# 09_Clock.net
KiCad netlist of a schematic drawn in Altium Designer
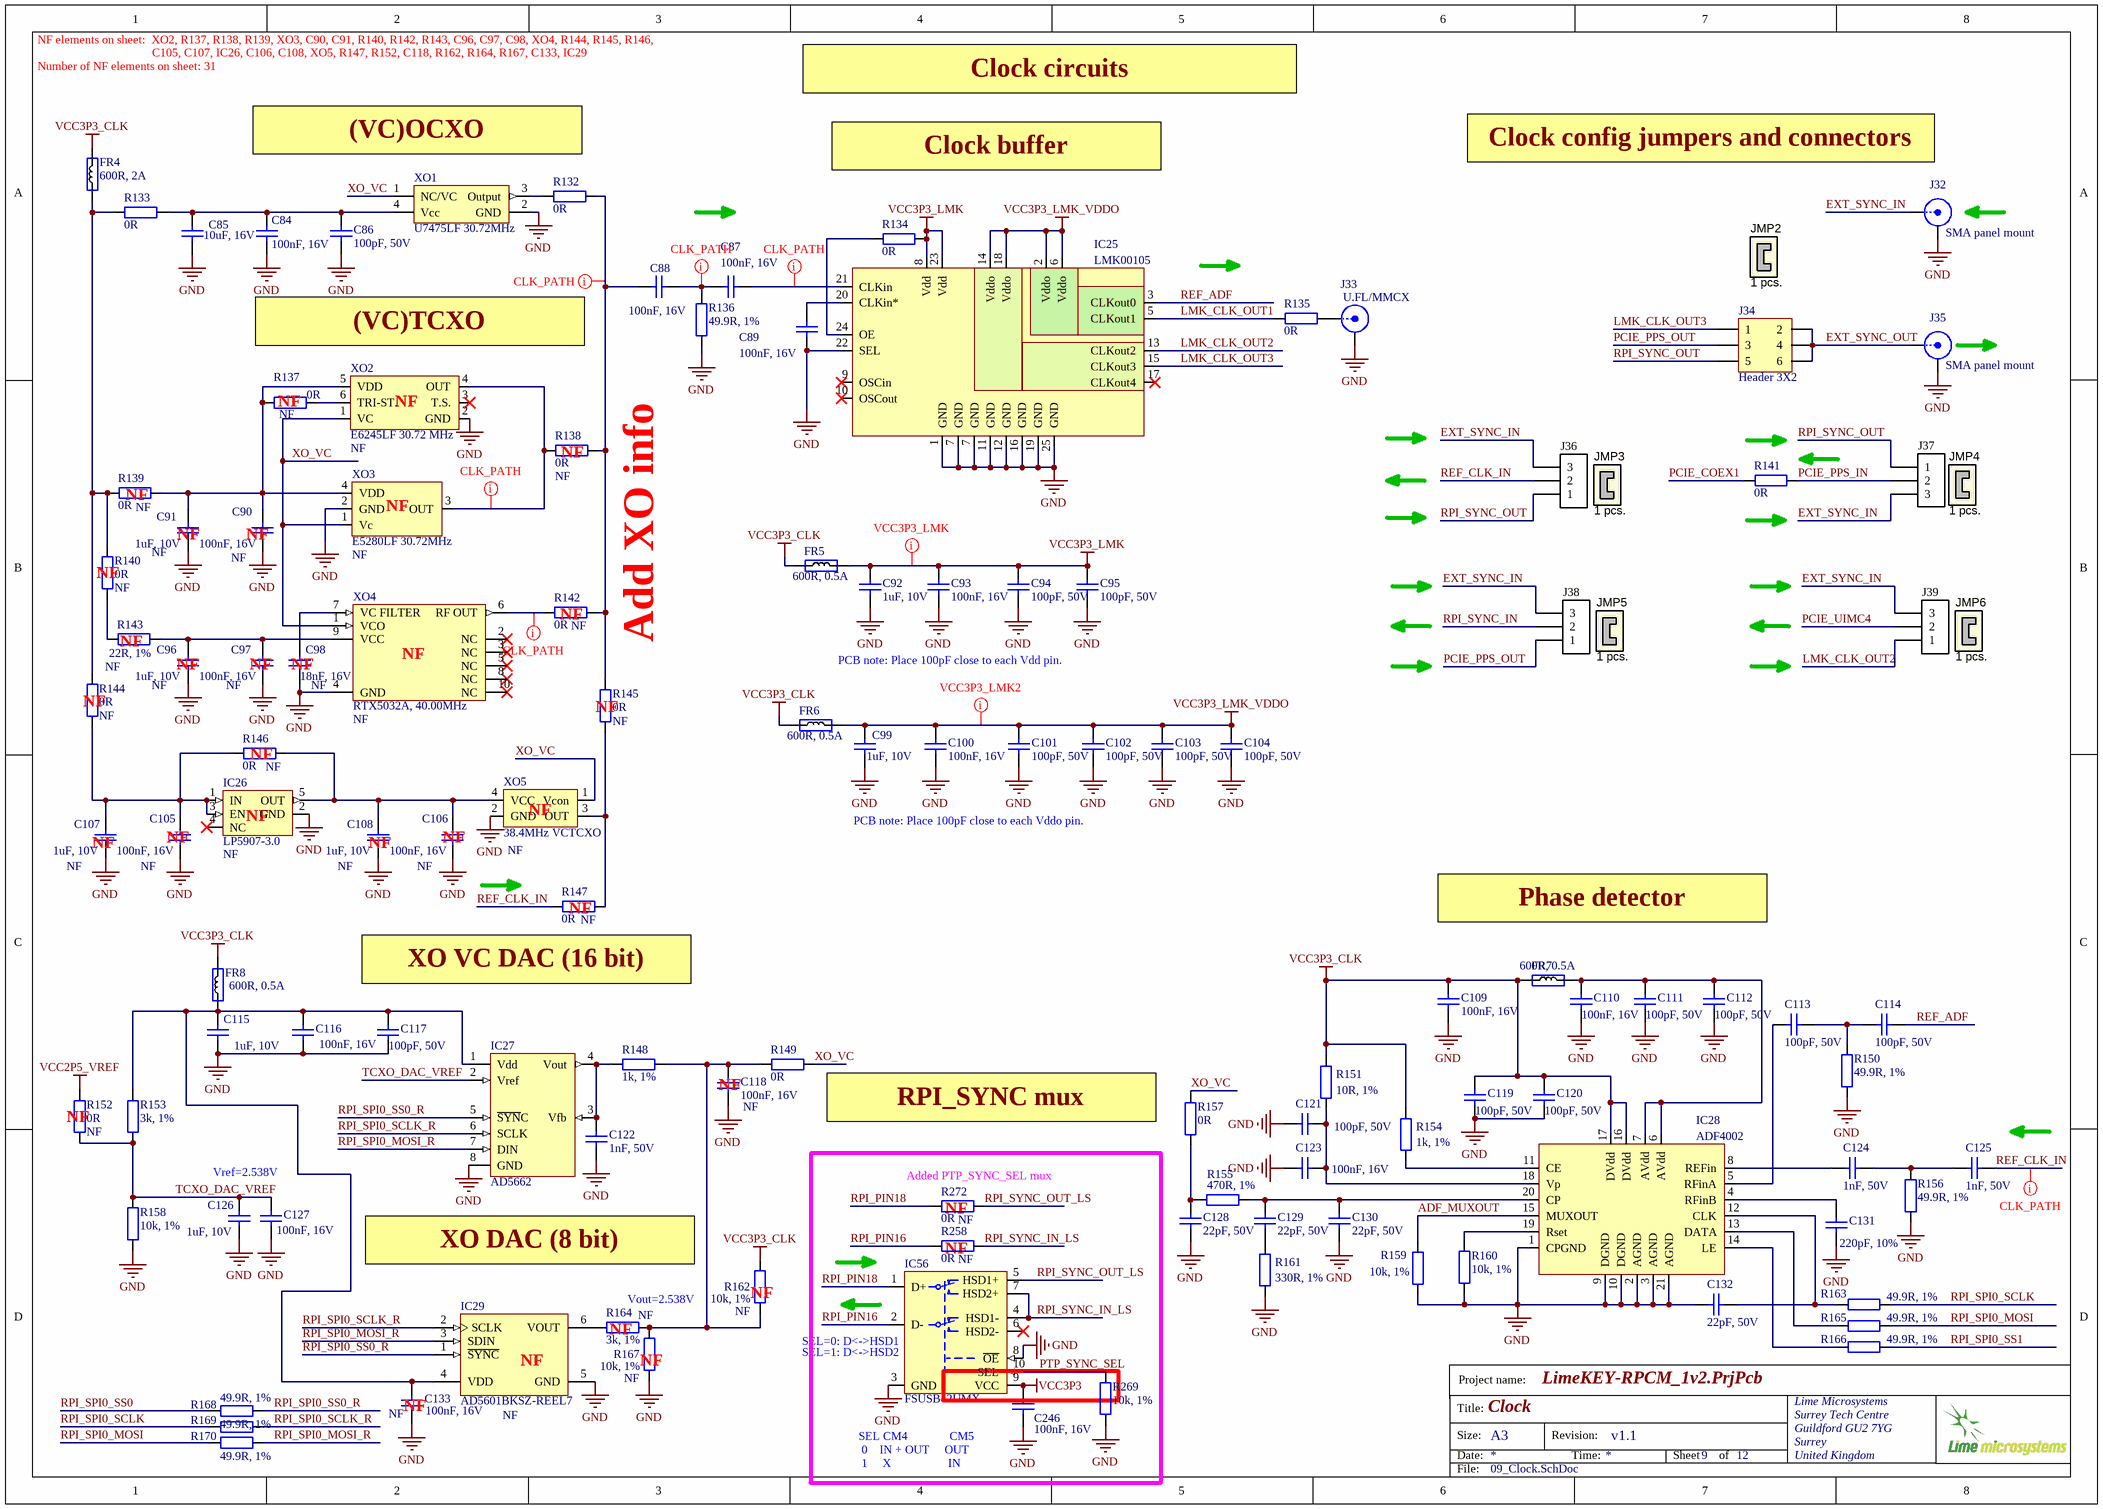
[diagram p0: 09_Clock.SchDoc]

(export (version "E")
  (design (tool "Eeschema 10.0.6"))
  (components
    (comp (ref "C84")
      (value "100nF, 16V")
      (footprint "CAP0402")
      (fields
        (field (name "MANUFACTURER") "Murata Electronics")
        (field (name "TOLERANCE") "10 %")
        (field (name "MANUFACTURER PART NUMBER") "GRM155R71C104KA88D")
      )
      (libsource (lib "LimeMicroAltiumLib_schLib") (part "Cap_0402"))
    )
    (comp (ref "C85")
      (value "10uF, 16V")
      (footprint "CAP0603")
      (fields (field (name "MANUFACTURER") "Yageo") (field (name "TOLERANCE") "±20%"))
      (libsource (lib "LimeMicroAltiumLib_schLib") (part "Cap_0603"))
    )
    (comp (ref "C86")
      (value "100pF, 50V")
      (footprint "CAP0402")
      (fields (field (name "TOLERANCE") "±5%") (field (name "MANUFACTURER") "Yageo"))
      (libsource (lib "LimeMicroAltiumLib_schLib") (part "Cap_0402"))
    )
    (comp (ref "C87")
      (value "100nF, 16V")
      (footprint "CAP0402")
      (fields
        (field (name "MANUFACTURER") "Murata Electronics")
        (field (name "TOLERANCE") "10 %")
        (field (name "MANUFACTURER PART NUMBER") "GRM155R71C104KA88D")
      )
      (libsource (lib "LimeMicroAltiumLib_schLib") (part "Cap_0402"))
    )
    (comp (ref "C88")
      (value "100nF, 16V")
      (footprint "CAP0402")
      (fields
        (field (name "MANUFACTURER") "Murata Electronics")
        (field (name "TOLERANCE") "10 %")
        (field (name "MANUFACTURER PART NUMBER") "GRM155R71C104KA88D")
      )
      (libsource (lib "LimeMicroAltiumLib_schLib") (part "Cap_0402"))
    )
    (comp (ref "C89")
      (value "100nF, 16V")
      (footprint "CAP0402")
      (fields
        (field (name "MANUFACTURER") "Murata Electronics")
        (field (name "TOLERANCE") "10 %")
        (field (name "MANUFACTURER PART NUMBER") "GRM155R71C104KA88D")
      )
      (libsource (lib "LimeMicroAltiumLib_schLib") (part "Cap_0402"))
    )
    (comp (ref "C90")
      (value "100nF, 16V")
      (footprint "CAP0402")
      (fields
        (field (name "ASSEMBLY INFO") "NF")
        (field (name "MANUFACTURER") "Murata Electronics")
        (field (name "TOLERANCE") "10 %")
        (field (name "MANUFACTURER PART NUMBER") "GRM155R71C104KA88D")
      )
      (libsource (lib "LimeMicroAltiumLib_schLib") (part "Cap_0402"))
    )
    (comp (ref "C91")
      (value "1uF, 10V")
      (footprint "CAP0402")
      (description "CAP CER 1UF 10V X5R 0402")
      (fields (field (name "ASSEMBLY INFO") "NF") (field (name "MANUFACTURER") "Yageo"))
      (libsource (lib "LimeMicroAltiumLib_schLib") (part "Cap_0402"))
    )
    (comp (ref "C92")
      (value "1uF, 10V")
      (footprint "CAP0402")
      (description "CAP CER 1UF 10V X5R 0402")
      (fields (field (name "MANUFACTURER") "Yageo") (field (name "TOLERANCE") "±20%"))
      (libsource (lib "LimeMicroAltiumLib_schLib") (part "Cap_0402"))
    )
    (comp (ref "C93")
      (value "100nF, 16V")
      (footprint "CAP0402")
      (fields
        (field (name "MANUFACTURER") "Murata Electronics")
        (field (name "TOLERANCE") "10 %")
        (field (name "MANUFACTURER PART NUMBER") "GRM155R71C104KA88D")
      )
      (libsource (lib "LimeMicroAltiumLib_schLib") (part "Cap_0402"))
    )
    (comp (ref "C94")
      (value "100pF, 50V")
      (footprint "CAP0402")
      (fields (field (name "MANUFACTURER") "Yageo") (field (name "TOLERANCE") "±5%"))
      (libsource (lib "LimeMicroAltiumLib_schLib") (part "Cap_0402"))
    )
    (comp (ref "C95")
      (value "100pF, 50V")
      (footprint "CAP0402")
      (fields (field (name "MANUFACTURER") "Yageo") (field (name "TOLERANCE") "±5%"))
      (libsource (lib "LimeMicroAltiumLib_schLib") (part "Cap_0402"))
    )
    (comp (ref "C96")
      (value "1uF, 10V")
      (footprint "CAP0402")
      (description "CAP CER 1UF 10V X5R 0402")
      (fields (field (name "ASSEMBLY INFO") "NF") (field (name "MANUFACTURER") "Yageo"))
      (libsource (lib "LimeMicroAltiumLib_schLib") (part "Cap_0402"))
    )
    (comp (ref "C97")
      (value "100nF, 16V")
      (footprint "CAP0402")
      (fields
        (field (name "ASSEMBLY INFO") "NF")
        (field (name "MANUFACTURER") "Murata Electronics")
        (field (name "TOLERANCE") "10 %")
        (field (name "MANUFACTURER PART NUMBER") "GRM155R71C104KA88D")
      )
      (libsource (lib "LimeMicroAltiumLib_schLib") (part "Cap_0402"))
    )
    (comp (ref "C98")
      (value "18nF, 16V")
      (footprint "CAP0402")
      (fields
        (field (name "ASSEMBLY INFO") "NF")
        (field (name "MANUFACTURER") "Yageo")
        (field (name "TOLERANCE") "±10%")
      )
      (libsource (lib "LimeMicroAltiumLib_schLib") (part "Cap_0402"))
    )
    (comp (ref "C99")
      (value "1uF, 10V")
      (footprint "CAP0402")
      (description "CAP CER 1UF 10V X5R 0402")
      (fields (field (name "MANUFACTURER") "Yageo") (field (name "TOLERANCE") "±20%"))
      (libsource (lib "LimeMicroAltiumLib_schLib") (part "Cap_0402"))
    )
    (comp (ref "C100")
      (value "100nF, 16V")
      (footprint "CAP0402")
      (fields
        (field (name "MANUFACTURER") "Murata Electronics")
        (field (name "TOLERANCE") "10 %")
        (field (name "MANUFACTURER PART NUMBER") "GRM155R71C104KA88D")
      )
      (libsource (lib "LimeMicroAltiumLib_schLib") (part "Cap_0402"))
    )
    (comp (ref "C101")
      (value "100pF, 50V")
      (footprint "CAP0402")
      (fields (field (name "MANUFACTURER") "Yageo") (field (name "TOLERANCE") "±5%"))
      (libsource (lib "LimeMicroAltiumLib_schLib") (part "Cap_0402"))
    )
    (comp (ref "C102")
      (value "100pF, 50V")
      (footprint "CAP0402")
      (fields (field (name "MANUFACTURER") "Yageo") (field (name "TOLERANCE") "±5%"))
      (libsource (lib "LimeMicroAltiumLib_schLib") (part "Cap_0402"))
    )
    (comp (ref "C103")
      (value "100pF, 50V")
      (footprint "CAP0402")
      (fields (field (name "MANUFACTURER") "Yageo") (field (name "TOLERANCE") "±5%"))
      (libsource (lib "LimeMicroAltiumLib_schLib") (part "Cap_0402"))
    )
    (comp (ref "C104")
      (value "100pF, 50V")
      (footprint "CAP0402")
      (fields (field (name "MANUFACTURER") "Yageo") (field (name "TOLERANCE") "±5%"))
      (libsource (lib "LimeMicroAltiumLib_schLib") (part "Cap_0402"))
    )
    (comp (ref "C105")
      (value "100nF, 16V")
      (footprint "CAP0402")
      (fields
        (field (name "ASSEMBLY INFO") "NF")
        (field (name "MANUFACTURER") "Murata Electronics")
        (field (name "TOLERANCE") "10 %")
        (field (name "MANUFACTURER PART NUMBER") "GRM155R71C104KA88D")
      )
      (libsource (lib "") (part "Cap_0402_1"))
    )
    (comp (ref "C106")
      (value "100nF, 16V")
      (footprint "CAP0402")
      (fields
        (field (name "ASSEMBLY INFO") "NF")
        (field (name "MANUFACTURER") "Murata Electronics")
        (field (name "TOLERANCE") "10 %")
        (field (name "MANUFACTURER PART NUMBER") "GRM155R71C104KA88D")
      )
      (libsource (lib "") (part "Cap_0402_1"))
    )
    (comp (ref "C107")
      (value "1uF, 10V")
      (footprint "CAP0402")
      (fields (field (name "ASSEMBLY INFO") "NF") (field (name "MANUFACTURER") "Yageo"))
      (libsource (lib "") (part "Cap_0402_1"))
    )
    (comp (ref "C108")
      (value "1uF, 10V")
      (footprint "CAP0402")
      (fields (field (name "ASSEMBLY INFO") "NF") (field (name "MANUFACTURER") "Yageo"))
      (libsource (lib "") (part "Cap_0402_1"))
    )
    (comp (ref "C109")
      (value "100nF, 16V")
      (footprint "CAP0402")
      (fields
        (field (name "MANUFACTURER") "Murata Electronics")
        (field (name "TOLERANCE") "10 %")
        (field (name "MANUFACTURER PART NUMBER") "GRM155R71C104KA88D")
      )
      (libsource (lib "LimeMicroAltiumLib_schLib") (part "Cap_0402"))
    )
    (comp (ref "C110")
      (value "100nF, 16V")
      (footprint "CAP0402")
      (fields
        (field (name "MANUFACTURER") "Murata Electronics")
        (field (name "TOLERANCE") "10 %")
        (field (name "MANUFACTURER PART NUMBER") "GRM155R71C104KA88D")
      )
      (libsource (lib "LimeMicroAltiumLib_schLib") (part "Cap_0402"))
    )
    (comp (ref "C111")
      (value "100pF, 50V")
      (footprint "CAP0402")
      (fields (field (name "MANUFACTURER") "Yageo") (field (name "TOLERANCE") "±5%"))
      (libsource (lib "LimeMicroAltiumLib_schLib") (part "Cap_0402"))
    )
    (comp (ref "C112")
      (value "100pF, 50V")
      (footprint "CAP0402")
      (fields (field (name "MANUFACTURER") "Yageo") (field (name "TOLERANCE") "±5%"))
      (libsource (lib "LimeMicroAltiumLib_schLib") (part "Cap_0402"))
    )
    (comp (ref "C113")
      (value "100pF, 50V")
      (footprint "CAP0402")
      (fields (field (name "MANUFACTURER") "Yageo") (field (name "TOLERANCE") "±5%"))
      (libsource (lib "LimeMicroAltiumLib_schLib") (part "Cap_0402"))
    )
    (comp (ref "C114")
      (value "100pF, 50V")
      (footprint "CAP0402")
      (fields (field (name "MANUFACTURER") "Yageo") (field (name "TOLERANCE") "±5%"))
      (libsource (lib "LimeMicroAltiumLib_schLib") (part "Cap_0402"))
    )
    (comp (ref "C115")
      (value "1uF, 10V")
      (footprint "CAP0402")
      (description "CAP CER 1UF 10V X5R 0402")
      (fields (field (name "MANUFACTURER") "Yageo") (field (name "TOLERANCE") "±20%"))
      (libsource (lib "LimeMicroAltiumLib_schLib") (part "Cap_0402"))
    )
    (comp (ref "C116")
      (value "100nF, 16V")
      (footprint "CAP0402")
      (fields
        (field (name "TOLERANCE") "10 %")
        (field (name "MANUFACTURER") "Murata Electronics")
        (field (name "MANUFACTURER PART NUMBER") "GRM155R71C104KA88D")
      )
      (libsource (lib "LimeFPGAboard_schLib") (part "Cap_0603"))
    )
    (comp (ref "C117")
      (value "100pF, 50V")
      (footprint "CAP0402")
      (fields (field (name "MANUFACTURER") "Yageo") (field (name "TOLERANCE") "±5%"))
      (libsource (lib "LimeMicroAltiumLib_schLib") (part "Cap_0402"))
    )
    (comp (ref "C118")
      (value "100nF, 16V")
      (footprint "CAP0402")
      (fields
        (field (name "ASSEMBLY INFO") "NF")
        (field (name "MANUFACTURER") "Murata Electronics")
        (field (name "TOLERANCE") "10 %")
        (field (name "MANUFACTURER PART NUMBER") "GRM155R71C104KA88D")
      )
      (libsource (lib "LimeMicroAltiumLib_schLib") (part "Cap_0402"))
    )
    (comp (ref "C119")
      (value "100pF, 50V")
      (footprint "CAP0402")
      (fields (field (name "MANUFACTURER") "Yageo") (field (name "TOLERANCE") "±5%"))
      (libsource (lib "LimeMicroAltiumLib_schLib") (part "Cap_0402"))
    )
    (comp (ref "C120")
      (value "100pF, 50V")
      (footprint "CAP0402")
      (fields (field (name "MANUFACTURER") "Yageo") (field (name "TOLERANCE") "±5%"))
      (libsource (lib "LimeMicroAltiumLib_schLib") (part "Cap_0402"))
    )
    (comp (ref "C121")
      (value "100pF, 50V")
      (footprint "CAP0402")
      (fields (field (name "MANUFACTURER") "Yageo") (field (name "TOLERANCE") "±5%"))
      (libsource (lib "LimeMicroAltiumLib_schLib") (part "Cap_0402"))
    )
    (comp (ref "C122")
      (value "1nF, 50V")
      (footprint "CAP0402")
      (fields
        (field (name "TOLERANCE") "±10%")
        (field (name "MANUFACTURER") "Murata Electronics North America")
      )
      (libsource (lib "LimeMicroAltiumLib_schLib") (part "Cap_0402"))
    )
    (comp (ref "C123")
      (value "100nF, 16V")
      (footprint "CAP0402")
      (fields
        (field (name "MANUFACTURER") "Murata Electronics")
        (field (name "TOLERANCE") "10 %")
        (field (name "MANUFACTURER PART NUMBER") "GRM155R71C104KA88D")
      )
      (libsource (lib "LimeMicroAltiumLib_schLib") (part "Cap_0402"))
    )
    (comp (ref "C124")
      (value "1nF, 50V")
      (footprint "CAP0402")
      (fields
        (field (name "TOLERANCE") "±10%")
        (field (name "MANUFACTURER") "Murata Electronics North America")
      )
      (libsource (lib "LimeMicroAltiumLib_schLib") (part "Cap_0402"))
    )
    (comp (ref "C125")
      (value "1nF, 50V")
      (footprint "CAP0402")
      (fields
        (field (name "TOLERANCE") "±10%")
        (field (name "MANUFACTURER") "Murata Electronics North America")
      )
      (libsource (lib "LimeMicroAltiumLib_schLib") (part "Cap_0402"))
    )
    (comp (ref "C126")
      (value "1uF, 10V")
      (footprint "CAP0402")
      (description "CAP CER 1UF 10V X5R 0402")
      (fields (field (name "MANUFACTURER") "Yageo") (field (name "TOLERANCE") "±20%"))
      (libsource (lib "LimeMicroAltiumLib_schLib") (part "Cap_0402"))
    )
    (comp (ref "C127")
      (value "100nF, 16V")
      (footprint "CAP0402")
      (fields
        (field (name "TOLERANCE") "10 %")
        (field (name "MANUFACTURER") "Murata Electronics")
        (field (name "MANUFACTURER PART NUMBER") "GRM155R71C104KA88D")
      )
      (libsource (lib "LimeFPGAboard_schLib") (part "Cap_0603"))
    )
    (comp (ref "C128")
      (value "22pF, 50V")
      (footprint "CAP0402")
      (fields (field (name "TOLERANCE") "±5%") (field (name "MANUFACTURER") "Yageo"))
      (libsource (lib "LimeMicroAltiumLib_schLib") (part "Cap_0402"))
    )
    (comp (ref "C129")
      (value "22pF, 50V")
      (footprint "CAP0402")
      (fields (field (name "TOLERANCE") "±5%") (field (name "MANUFACTURER") "Yageo"))
      (libsource (lib "LimeMicroAltiumLib_schLib") (part "Cap_0402"))
    )
    (comp (ref "C130")
      (value "22pF, 50V")
      (footprint "CAP0402")
      (fields (field (name "TOLERANCE") "±5%") (field (name "MANUFACTURER") "Yageo"))
      (libsource (lib "LimeMicroAltiumLib_schLib") (part "Cap_0402"))
    )
    (comp (ref "C131")
      (value "220pF, 10%")
      (footprint "CAP0402")
      (fields (field (name "MANUFACTURER") "Yageo") (field (name "TOLERANCE") "±10%"))
      (libsource (lib "LimeMicroAltiumLib_schLib") (part "Cap_0402"))
    )
    (comp (ref "C132")
      (value "22pF, 50V")
      (footprint "CAP0402")
      (fields (field (name "TOLERANCE") "±5%") (field (name "MANUFACTURER") "Yageo"))
      (libsource (lib "LimeMicroAltiumLib_schLib") (part "Cap_0402"))
    )
    (comp (ref "C133")
      (value "100nF, 16V")
      (footprint "CAP0402")
      (fields
        (field (name "TOLERANCE") "10 %")
        (field (name "MANUFACTURER") "Murata Electronics")
        (field (name "MANUFACTURER PART NUMBER") "GRM155R71C104KA88D")
        (field (name "ASSEMBLY INFO") "NF")
      )
      (libsource (lib "LimeFPGAboard_schLib") (part "Cap_0603"))
    )
    (comp (ref "C246")
      (value "100nF, 16V")
      (footprint "CAP0402")
      (fields
        (field (name "MANUFACTURER") "Murata Electronics")
        (field (name "TOLERANCE") "10 %")
        (field (name "MANUFACTURER PART NUMBER") "GRM155R71C104KA88D")
      )
      (libsource (lib "LimeMicroAltiumLib_schLib") (part "Cap_0402"))
    )
    (comp (ref "FR4")
      (value "600R, 2A")
      (footprint "RES0805")
      (fields (field (name "MANUFACTURER") "TDK Corporation"))
      (libsource (lib "LimeFPGAboard_schLib") (part "Ferrite"))
    )
    (comp (ref "FR5")
      (value "600R, 0.5A")
      (footprint "RES0402")
      (fields (field (name "MANUFACTURER") "Murata") (field (name "TOLERANCE") "25%"))
      (libsource (lib "LimeMicroAltiumLib_schLib") (part "Ferrite"))
    )
    (comp (ref "FR6")
      (value "600R, 0.5A")
      (footprint "RES0402")
      (fields (field (name "MANUFACTURER") "Murata") (field (name "TOLERANCE") "25%"))
      (libsource (lib "LimeMicroAltiumLib_schLib") (part "Ferrite"))
    )
    (comp (ref "FR7")
      (value "600R, 0.5A")
      (footprint "RES0402")
      (fields (field (name "MANUFACTURER") "Murata") (field (name "TOLERANCE") "25%"))
      (libsource (lib "LimeMicroAltiumLib_schLib") (part "Ferrite"))
    )
    (comp (ref "FR8")
      (value "600R, 0.5A")
      (footprint "RES0402")
      (fields (field (name "MANUFACTURER") "Murata") (field (name "TOLERANCE") "25%"))
      (libsource (lib "LimeMicroAltiumLib_schLib") (part "Ferrite"))
    )
    (comp (ref "IC25")
      (value "LMK00105")
      (footprint "LMK00105SQ")
      (fields (field (name "MANUFACTURER") "Texas Instruments"))
      (libsource (lib "LimeMicroAltiumLib_schLib") (part "LMK00105"))
    )
    (comp (ref "IC26")
      (value "LP5907-3.0")
      (footprint "SOT23-5")
      (fields (field (name "MANUFACTURER") "Texas Instruments") (field (name "ASSEMBLY INFO") "NF"))
      (libsource (lib "LimeMicroAltiumLib_schLib_r01") (part "LP5907"))
    )
    (comp (ref "IC27")
      (value "AD5662")
      (footprint "AD5662_SOT23-8")
      (fields (field (name "MANUFACTURER") "Analog Devices Inc."))
      (libsource (lib "LimeMicroAltiumLib_schLib") (part "AD5662"))
    )
    (comp (ref "IC28")
      (value "ADF4002")
      (footprint "ADF4002")
      (fields (field (name "MANUFACTURER") "Analog Devices Inc"))
      (libsource (lib "LimeMicroAltiumLib_schLib") (part "ADF4002"))
    )
    (comp (ref "IC29")
      (value "AD5601BKSZ-REEL7")
      (footprint "AD5601_SOT23-6")
      (fields
        (field (name "GENERIC PART NUMBER") "AD5601")
        (field (name "MANUFACTURER") "Analog Devices")
        (field (name "ASSEMBLY INFO") "NF")
      )
      (libsource (lib "LimeMicroAltiumLib_schLib") (part "AD5601BKSZ-REEL7"))
    )
    (comp (ref "IC56")
      (value "FSUSB42UMX")
      (footprint "FSUSB42UMX")
      (fields (field (name "MANUFACTURER") "ON Semiconductor") (field (name "BASE PART NUMBER") "FSUSB42"))
      (libsource (lib "LimeMicroAltiumLib_schLib_r01") (part "FSUSB42UMX"))
    )
    (comp (ref "J32")
      (value "SMA panel mount")
      (footprint "SMA_connector_side")
      (description "CONN SMA JACK STR 50OHM EDGE MNT")
      (fields (field (name "MANUFACTURER") "Linx"))
      (libsource (lib "LimeMicroAltiumLib_schLib") (part "RF_IF_connector"))
    )
    (comp (ref "J33")
      (value "U.FL/MMCX")
      (footprint "MMCX_UFL_conn_u")
      (description "CONN UMC RCPT STR 50 OHM SMD")
      (fields (field (name "MANUFACTURER") "Molex, LLC"))
      (libsource (lib "") (part "RF_IF_connector_1"))
    )
    (comp (ref "J34")
      (value "Header 3X2")
      (footprint "Header3x2")
      (description "Header, 2-Pin, Dual row")
      (fields
        (field (name "MANUFACTURER PART NUMBER") "PH2-06-UA")
        (field (name "MANUFACTURER") "Adam Equipment")
      )
      (libsource (lib "LimeMicroAltiumLib_schLib_r01") (part "Header 3X2"))
    )
    (comp (ref "J35")
      (value "SMA panel mount")
      (footprint "SMA_connector_side")
      (description "CONN SMA JACK STR 50OHM EDGE MNT")
      (fields (field (name "MANUFACTURER") "Linx"))
      (libsource (lib "LimeMicroAltiumLib_schLib") (part "RF_IF_connector"))
    )
    (comp (ref "J36")
      (value "Header 3x1 pin")
      (footprint "HDR_1x3")
      (description "Header, 3-pin")
      (fields
        (field (name "MANUFACTURER PART NUMBER") "61300311121")
        (field (name "MANUFACTURER") "Wurth Electronics")
      )
      (libsource (lib "") (part "Header3P_1"))
    )
    (comp (ref "J37")
      (value "Header 3x1 pin")
      (footprint "HDR_1x3")
      (description "Header, 3-pin")
      (fields
        (field (name "MANUFACTURER PART NUMBER") "61300311121")
        (field (name "MANUFACTURER") "Wurth Electronics")
      )
      (libsource (lib "LimeMicroAltiumLib_schLib_r04") (part "Header3P"))
    )
    (comp (ref "J38")
      (value "Header 3x1 pin")
      (footprint "HDR_1x3")
      (description "Header, 3-pin")
      (fields
        (field (name "MANUFACTURER PART NUMBER") "61300311121")
        (field (name "MANUFACTURER") "Wurth Electronics")
      )
      (libsource (lib "") (part "Header3P_1"))
    )
    (comp (ref "J39")
      (value "Header 3x1 pin")
      (footprint "HDR_1x3")
      (description "Header, 3-pin")
      (fields
        (field (name "MANUFACTURER PART NUMBER") "61300311121")
        (field (name "MANUFACTURER") "Wurth Electronics")
      )
      (libsource (lib "") (part "Header3P_1"))
    )
    (comp (ref "JMP2")
      (value "1 pcs.")
      (description "Shorting Jumper, 2-position, 1.27mm pitch")
      (fields (field (name "MANUFACTURER") "Sullins"))
      (libsource (lib "LimeMicroAltiumLib_schLib") (part "JUMP_2P_CONN_HEADER"))
    )
    (comp (ref "JMP3")
      (value "1 pcs.")
      (description "Shorting Jumper, 2-position, 1.27mm pitch")
      (fields (field (name "MANUFACTURER") "Sullins"))
      (libsource (lib "LimeMicroAltiumLib_schLib") (part "JUMP_2P_CONN_HEADER"))
    )
    (comp (ref "JMP4")
      (value "1 pcs.")
      (description "Shorting Jumper, 2-position, 1.27mm pitch")
      (fields (field (name "MANUFACTURER") "Sullins"))
      (libsource (lib "LimeMicroAltiumLib_schLib") (part "JUMP_2P_CONN_HEADER"))
    )
    (comp (ref "JMP5")
      (value "1 pcs.")
      (description "Shorting Jumper, 2-position, 1.27mm pitch")
      (fields (field (name "MANUFACTURER") "Sullins"))
      (libsource (lib "LimeMicroAltiumLib_schLib") (part "JUMP_2P_CONN_HEADER"))
    )
    (comp (ref "JMP6")
      (value "1 pcs.")
      (description "Shorting Jumper, 2-position, 1.27mm pitch")
      (fields (field (name "MANUFACTURER") "Sullins"))
      (libsource (lib "LimeMicroAltiumLib_schLib") (part "JUMP_2P_CONN_HEADER"))
    )
    (comp (ref "R132")
      (value "0R")
      (footprint "RES0402_v2")
      (fields (field (name "MANUFACTURER") "Yageo") (field (name "TOLERANCE") "Jumper"))
      (libsource (lib "LimeMicroAltiumLib_schLib") (part "Res_0402"))
    )
    (comp (ref "R133")
      (value "0R")
      (footprint "RES0402")
      (fields (field (name "MANUFACTURER") "Yageo") (field (name "TOLERANCE") "Jumper"))
      (libsource (lib "LimeMicroAltiumLib_schLib") (part "Res_0402"))
    )
    (comp (ref "R134")
      (value "0R")
      (footprint "RES0402")
      (fields (field (name "MANUFACTURER") "Yageo") (field (name "TOLERANCE") "Jumper"))
      (libsource (lib "LimeMicroAltiumLib_schLib") (part "Res_0402"))
    )
    (comp (ref "R135")
      (value "0R")
      (footprint "RES0402")
      (fields (field (name "MANUFACTURER") "Yageo") (field (name "TOLERANCE") "Jumper"))
      (libsource (lib "") (part "Res_0402_1"))
    )
    (comp (ref "R136")
      (value "49.9R, 1%")
      (footprint "RES0402")
      (fields
        (field (name "TOLERANCE") "±1%")
        (field (name "MANUFACTURER") "Samsung Electro-Mechanics America, Inc.")
      )
      (libsource (lib "LimeMicroAltiumLib_schLib") (part "Res_0402"))
    )
    (comp (ref "R137")
      (value "0R")
      (footprint "RES0402")
      (fields
        (field (name "ASSEMBLY INFO") "NF")
        (field (name "MANUFACTURER") "Yageo")
        (field (name "TOLERANCE") "Jumper")
      )
      (libsource (lib "LimeMicroAltiumLib_schLib") (part "Res_0402"))
    )
    (comp (ref "R138")
      (value "0R")
      (footprint "RES0402_v2")
      (fields
        (field (name "ASSEMBLY INFO") "NF")
        (field (name "MANUFACTURER") "Yageo")
        (field (name "TOLERANCE") "Jumper")
      )
      (libsource (lib "LimeMicroAltiumLib_schLib") (part "Res_0402"))
    )
    (comp (ref "R139")
      (value "0R")
      (footprint "RES0402")
      (fields
        (field (name "MANUFACTURER") "Yageo")
        (field (name "TOLERANCE") "Jumper")
        (field (name "ASSEMBLY INFO") "NF")
      )
      (libsource (lib "LimeMicroAltiumLib_schLib") (part "Res_0402"))
    )
    (comp (ref "R140")
      (value "0R")
      (footprint "RES0402")
      (fields
        (field (name "ASSEMBLY INFO") "NF")
        (field (name "MANUFACTURER") "Yageo")
        (field (name "TOLERANCE") "Jumper")
      )
      (libsource (lib "LimeMicroAltiumLib_schLib") (part "Res_0402"))
    )
    (comp (ref "R141")
      (value "0R")
      (footprint "RES0402")
      (fields (field (name "MANUFACTURER") "Yageo") (field (name "TOLERANCE") "Jumper"))
      (libsource (lib "") (part "Res_0402_1"))
    )
    (comp (ref "R142")
      (value "0R")
      (footprint "RES0402_v2")
      (fields
        (field (name "ASSEMBLY INFO") "NF")
        (field (name "MANUFACTURER") "Yageo")
        (field (name "TOLERANCE") "Jumper")
      )
      (libsource (lib "LimeMicroAltiumLib_schLib") (part "Res_0402"))
    )
    (comp (ref "R143")
      (value "22R, 1%")
      (footprint "RES0402")
      (fields
        (field (name "TOLERANCE") "±1%")
        (field (name "MANUFACTURER") "Yageo")
        (field (name "ASSEMBLY INFO") "NF")
      )
      (libsource (lib "LimeFPGAboard_schLib") (part "Res_0402"))
    )
    (comp (ref "R144")
      (value "0R")
      (footprint "RES0402")
      (fields
        (field (name "MANUFACTURER") "Yageo")
        (field (name "TOLERANCE") "Jumper")
        (field (name "ASSEMBLY INFO") "NF")
      )
      (libsource (lib "") (part "Res_0402_1"))
    )
    (comp (ref "R145")
      (value "0R")
      (footprint "RES0402_v2")
      (fields
        (field (name "ASSEMBLY INFO") "NF")
        (field (name "MANUFACTURER") "Yageo")
        (field (name "TOLERANCE") "Jumper")
      )
      (libsource (lib "") (part "Res_0402_1"))
    )
    (comp (ref "R146")
      (value "0R")
      (footprint "RES0402")
      (fields
        (field (name "MANUFACTURER") "Yageo")
        (field (name "TOLERANCE") "Jumper")
        (field (name "ASSEMBLY INFO") "NF")
      )
      (libsource (lib "") (part "Res_0402_1"))
    )
    (comp (ref "R147")
      (value "0R")
      (footprint "RES0402_v2")
      (fields
        (field (name "ASSEMBLY INFO") "NF")
        (field (name "MANUFACTURER") "Yageo")
        (field (name "TOLERANCE") "Jumper")
      )
      (libsource (lib "LimeMicroAltiumLib_schLib") (part "Res_0402"))
    )
    (comp (ref "R148")
      (value "1k, 1%")
      (footprint "RES0402")
      (fields (field (name "MANUFACTURER") "Stackpole Electronics Inc") (field (name "TOLERANCE") "±1%"))
      (libsource (lib "LimeMicroAltiumLib_schLib") (part "Res_0402"))
    )
    (comp (ref "R149")
      (value "0R")
      (footprint "RES0402")
      (fields (field (name "MANUFACTURER") "Yageo") (field (name "TOLERANCE") "Jumper"))
      (libsource (lib "LimeMicroAltiumLib_schLib") (part "Res_0402"))
    )
    (comp (ref "R150")
      (value "49.9R, 1%")
      (footprint "RES0402")
      (fields
        (field (name "TOLERANCE") "±1%")
        (field (name "MANUFACTURER") "Samsung Electro-Mechanics America, Inc.")
      )
      (libsource (lib "LimeMicroAltiumLib_schLib") (part "Res_0402"))
    )
    (comp (ref "R151")
      (value "10R, 1%")
      (footprint "RES0402")
      (fields (field (name "MANUFACTURER") "Stackpole Electronics") (field (name "TOLERANCE") "1%"))
      (libsource (lib "LimeMicroAltiumLib_schLib") (part "Res_0402"))
    )
    (comp (ref "R152")
      (value "0R")
      (footprint "RES0402_v2")
      (fields
        (field (name "ASSEMBLY INFO") "NF")
        (field (name "MANUFACTURER") "Yageo")
        (field (name "TOLERANCE") "Jumper")
      )
      (libsource (lib "LimeMicroAltiumLib_schLib") (part "Res_0402"))
    )
    (comp (ref "R153")
      (value "3k, 1%")
      (footprint "RES0402")
      (fields (field (name "TOLERANCE") "±1%") (field (name "MANUFACTURER") "Vishay Dale"))
      (libsource (lib "LimeMicroAltiumLib_schLib") (part "Res_0402"))
    )
    (comp (ref "R154")
      (value "1k, 1%")
      (footprint "RES0402")
      (fields (field (name "MANUFACTURER") "Stackpole Electronics Inc") (field (name "TOLERANCE") "±1%"))
      (libsource (lib "LimeMicroAltiumLib_schLib") (part "Res_0402"))
    )
    (comp (ref "R155")
      (value "470R, 1%")
      (footprint "RES0402")
      (fields (field (name "TOLERANCE") "1%") (field (name "MANUFACTURER") "Yageo"))
      (libsource (lib "") (part "Res_0402_1"))
    )
    (comp (ref "R156")
      (value "49.9R, 1%")
      (footprint "RES0402")
      (fields
        (field (name "TOLERANCE") "±1%")
        (field (name "MANUFACTURER") "Samsung Electro-Mechanics America, Inc.")
      )
      (libsource (lib "LimeMicroAltiumLib_schLib") (part "Res_0402"))
    )
    (comp (ref "R157")
      (value "0R")
      (footprint "RES0402")
      (fields (field (name "MANUFACTURER") "Yageo") (field (name "TOLERANCE") "Jumper"))
      (libsource (lib "LimeMicroAltiumLib_schLib") (part "Res_0402"))
    )
    (comp (ref "R158")
      (value "10k, 1%")
      (footprint "RES0402")
      (fields (field (name "MANUFACTURER") "Yageo") (field (name "TOLERANCE") "±1%"))
      (libsource (lib "LimeMicroAltiumLib_schLib") (part "Res_0402"))
    )
    (comp (ref "R159")
      (value "10k, 1%")
      (footprint "RES0402")
      (fields (field (name "MANUFACTURER") "Yageo") (field (name "TOLERANCE") "±1%"))
      (libsource (lib "LimeMicroAltiumLib_schLib") (part "Res_0402"))
    )
    (comp (ref "R160")
      (value "10k, 1%")
      (footprint "RES0402")
      (fields (field (name "MANUFACTURER") "Yageo") (field (name "TOLERANCE") "±1%"))
      (libsource (lib "LimeMicroAltiumLib_schLib") (part "Res_0402"))
    )
    (comp (ref "R161")
      (value "330R, 1%")
      (footprint "RES0402")
      (fields (field (name "MANUFACTURER") "Yageo") (field (name "TOLERANCE") "1%"))
      (libsource (lib "LimeMicroAltiumLib_schLib") (part "Res_0402"))
    )
    (comp (ref "R162")
      (value "10k, 1%")
      (footprint "RES0402")
      (fields
        (field (name "ASSEMBLY INFO") "NF")
        (field (name "MANUFACTURER") "Yageo")
        (field (name "TOLERANCE") "±1%")
      )
      (libsource (lib "LimeMicroAltiumLib_schLib") (part "Res_0402"))
    )
    (comp (ref "R163")
      (value "49.9R, 1%")
      (footprint "RES0402")
      (fields
        (field (name "TOLERANCE") "±1%")
        (field (name "MANUFACTURER") "Samsung Electro-Mechanics America, Inc.")
      )
      (libsource (lib "LimeMicroAltiumLib_schLib") (part "Res_0402"))
    )
    (comp (ref "R164")
      (value "3k, 1%")
      (footprint "RES0402")
      (fields
        (field (name "ASSEMBLY INFO") "NF")
        (field (name "TOLERANCE") "±1%")
        (field (name "MANUFACTURER") "Vishay Dale")
      )
      (libsource (lib "LimeMicroAltiumLib_schLib") (part "Res_0402"))
    )
    (comp (ref "R165")
      (value "49.9R, 1%")
      (footprint "RES0402")
      (fields
        (field (name "TOLERANCE") "±1%")
        (field (name "MANUFACTURER") "Samsung Electro-Mechanics America, Inc.")
      )
      (libsource (lib "LimeMicroAltiumLib_schLib") (part "Res_0402"))
    )
    (comp (ref "R166")
      (value "49.9R, 1%")
      (footprint "RES0402")
      (fields
        (field (name "TOLERANCE") "±1%")
        (field (name "MANUFACTURER") "Samsung Electro-Mechanics America, Inc.")
      )
      (libsource (lib "LimeMicroAltiumLib_schLib") (part "Res_0402"))
    )
    (comp (ref "R167")
      (value "10k, 1%")
      (footprint "RES0402")
      (fields
        (field (name "ASSEMBLY INFO") "NF")
        (field (name "MANUFACTURER") "Yageo")
        (field (name "TOLERANCE") "±1%")
      )
      (libsource (lib "LimeMicroAltiumLib_schLib") (part "Res_0402"))
    )
    (comp (ref "R168")
      (value "49.9R, 1%")
      (footprint "RES0402")
      (fields
        (field (name "TOLERANCE") "±1%")
        (field (name "MANUFACTURER") "Samsung Electro-Mechanics America, Inc.")
      )
      (libsource (lib "LimeMicroAltiumLib_schLib") (part "Res_0402"))
    )
    (comp (ref "R169")
      (value "49.9R, 1%")
      (footprint "RES0402")
      (fields
        (field (name "TOLERANCE") "±1%")
        (field (name "MANUFACTURER") "Samsung Electro-Mechanics America, Inc.")
      )
      (libsource (lib "LimeMicroAltiumLib_schLib") (part "Res_0402"))
    )
    (comp (ref "R170")
      (value "49.9R, 1%")
      (footprint "RES0402")
      (fields
        (field (name "TOLERANCE") "±1%")
        (field (name "MANUFACTURER") "Samsung Electro-Mechanics America, Inc.")
      )
      (libsource (lib "LimeMicroAltiumLib_schLib") (part "Res_0402"))
    )
    (comp (ref "R258")
      (value "0R")
      (footprint "RES0402")
      (fields
        (field (name "ASSEMBLY INFO") "NF")
        (field (name "MANUFACTURER") "Yageo")
        (field (name "TOLERANCE") "Jumper")
      )
      (libsource (lib "") (part "Res_0402_1"))
    )
    (comp (ref "R269")
      (value "10k, 1%")
      (footprint "RES0402")
      (fields (field (name "MANUFACTURER") "Yageo") (field (name "TOLERANCE") "±1%"))
      (libsource (lib "LimeMicroAltiumLib_schLib") (part "Res_0402"))
    )
    (comp (ref "R272")
      (value "0R")
      (footprint "RES0402")
      (fields
        (field (name "ASSEMBLY INFO") "NF")
        (field (name "MANUFACTURER") "Yageo")
        (field (name "TOLERANCE") "Jumper")
      )
      (libsource (lib "") (part "Res_0402_1"))
    )
    (comp (ref "XO1")
      (value "U7475LF 30.72MHz")
      (footprint "AOCJYR-10.000MHz")
      (fields (field (name "MANUFACTURER") "Rakon"))
      (libsource (lib "LimeMicroAltiumLib_schLib") (part "AOCJYR-10.000MHz"))
    )
    (comp (ref "XO2")
      (value "E6245LF 30.72 MHz")
      (footprint "RAKON_RPT7050A")
      (fields (field (name "ASSEMBLY INFO") "NF") (field (name "MANUFACTURER") "Rakon"))
      (libsource (lib "LimeMicroAltiumLib_schLib") (part "RPT7050A"))
    )
    (comp (ref "XO3")
      (value "E5280LF 30.72MHz")
      (footprint "RAKON_TXCO")
      (fields (field (name "ASSEMBLY INFO") "NF") (field (name "MANUFACTURER") "Rakon"))
      (libsource (lib "LimeMicroAltiumLib_schLib") (part "TXCO"))
    )
    (comp (ref "XO4")
      (value "RTX5032A, 40.00MHz")
      (footprint "RAKON_RTX5032A")
      (fields (field (name "ASSEMBLY INFO") "NF") (field (name "MANUFACTURER") "Rakon"))
      (libsource (lib "LimeMicroAltiumLib_schLib") (part "Rakon_RTX5032A"))
    )
    (comp (ref "XO5")
      (value "38.4MHz VCTCXO")
      (footprint "CRYSTAL_4-LCC_2P5x2P0")
      (description "Oscillator Crystal")
      (fields (field (name "MANUFACTURER") "Abracon") (field (name "ASSEMBLY INFO") "NF"))
      (libsource (lib "LimeMicroAltiumLib_schLib_r01") (part "ASVTX-12-A-38.400MHZ-H10-T_CRYSTAL"))
    )
  )
  (nets
    (net (code "1") (name "/ADF_MUXOUT") (class "Default")
      (node (ref "IC28") (pin "15") (pinfunction "MUXOUT_15") (pintype "passive"))
      (node (ref "R159") (pin "1") (pinfunction "1_1") (pintype "passive"))
    )
    (net (code "2") (name "/EXT_SYNC_IN") (class "Default")
      (node (ref "J32") (pin "1") (pinfunction "X_1") (pintype "passive"))
      (node (ref "J36") (pin "3") (pinfunction "3_3") (pintype "passive"))
      (node (ref "J37") (pin "3") (pinfunction "3_3") (pintype "passive"))
      (node (ref "J38") (pin "3") (pinfunction "3_3") (pintype "passive"))
      (node (ref "J39") (pin "3") (pinfunction "3_3") (pintype "passive"))
    )
    (net (code "3") (name "/EXT_SYNC_OUT") (class "Default")
      (node (ref "J34") (pin "2") (pinfunction "2_2") (pintype "passive"))
      (node (ref "J34") (pin "4") (pinfunction "4_4") (pintype "passive"))
      (node (ref "J34") (pin "6") (pinfunction "6_6") (pintype "passive"))
      (node (ref "J35") (pin "1") (pinfunction "X_1") (pintype "passive"))
    )
    (net (code "4") (name "/LMK_CLK_OUT1") (class "Default")
      (node (ref "IC25") (pin "5") (pinfunction "CLKout1_5") (pintype "passive"))
      (node (ref "R135") (pin "2") (pinfunction "2_2") (pintype "passive"))
    )
    (net (code "5") (name "/LMK_CLK_OUT2") (class "Default")
      (node (ref "IC25") (pin "13") (pinfunction "CLKout2_13") (pintype "passive"))
      (node (ref "J39") (pin "1") (pinfunction "1_1") (pintype "passive"))
    )
    (net (code "6") (name "/LMK_CLK_OUT3") (class "Default")
      (node (ref "IC25") (pin "15") (pinfunction "CLKout3_15") (pintype "passive"))
      (node (ref "J34") (pin "1") (pinfunction "1_1") (pintype "passive"))
    )
    (net (code "7") (name "/PCIE_COEX1") (class "Default")
      (node (ref "R141") (pin "2") (pinfunction "2_2") (pintype "passive"))
    )
    (net (code "9") (name "/PCIE_PPS_OUT") (class "Default")
      (node (ref "J34") (pin "3") (pinfunction "3_3") (pintype "passive"))
      (node (ref "J38") (pin "1") (pinfunction "1_1") (pintype "passive"))
    )
    (net (code "10") (name "/PCIE_UIMC4") (class "Default")
      (node (ref "J39") (pin "2") (pinfunction "2_2") (pintype "passive"))
    )
    (net (code "11") (name "/PTP_SYNC_SEL") (class "Default")
      (node (ref "IC56") (pin "10") (pinfunction "SEL_10") (pintype "input"))
      (node (ref "R269") (pin "1") (pinfunction "1_1") (pintype "passive"))
    )
    (net (code "12") (name "/REF_ADF") (class "Default")
      (node (ref "C114") (pin "2") (pinfunction "2_2") (pintype "passive"))
      (node (ref "IC25") (pin "3") (pinfunction "CLKout0_3") (pintype "passive"))
    )
    (net (code "13") (name "/REF_CLK_IN") (class "Default")
      (node (ref "C125") (pin "2") (pinfunction "2_2") (pintype "passive"))
      (node (ref "J36") (pin "2") (pinfunction "2_2") (pintype "passive"))
      (node (ref "R147") (pin "2") (pinfunction "2_2") (pintype "passive"))
    )
    (net (code "14") (name "/RPI_PIN16") (class "Default")
      (node (ref "IC56") (pin "2") (pinfunction "D-_2") (pintype "passive"))
      (node (ref "R258") (pin "2") (pinfunction "2_2") (pintype "passive"))
    )
    (net (code "15") (name "/RPI_PIN18") (class "Default")
      (node (ref "IC56") (pin "1") (pinfunction "D+_1") (pintype "passive"))
      (node (ref "R272") (pin "2") (pinfunction "2_2") (pintype "passive"))
    )
    (net (code "16") (name "/RPI_SPI0_MOSI") (class "Default")
      (node (ref "R165") (pin "1") (pinfunction "1_1") (pintype "passive"))
      (node (ref "R170") (pin "2") (pinfunction "2_2") (pintype "passive"))
    )
    (net (code "17") (name "/RPI_SPI0_MOSI_R") (class "Default")
      (node (ref "IC27") (pin "7") (pinfunction "DIN_7") (pintype "input"))
      (node (ref "IC29") (pin "3") (pinfunction "SDIN_3") (pintype "input"))
      (node (ref "R170") (pin "1") (pinfunction "1_1") (pintype "passive"))
    )
    (net (code "18") (name "/RPI_SPI0_SCLK") (class "Default")
      (node (ref "R163") (pin "1") (pinfunction "1_1") (pintype "passive"))
      (node (ref "R169") (pin "2") (pinfunction "2_2") (pintype "passive"))
    )
    (net (code "19") (name "/RPI_SPI0_SCLK_R") (class "Default")
      (node (ref "IC27") (pin "6") (pinfunction "SCLK_6") (pintype "input"))
      (node (ref "IC29") (pin "2") (pinfunction "SCLK_2") (pintype "input"))
      (node (ref "R169") (pin "1") (pinfunction "1_1") (pintype "passive"))
    )
    (net (code "20") (name "/RPI_SPI0_SS0") (class "Default")
      (node (ref "R168") (pin "2") (pinfunction "2_2") (pintype "passive"))
    )
    (net (code "21") (name "/RPI_SPI0_SS0_R") (class "Default")
      (node (ref "IC27") (pin "5") (pinfunction "~{SYN}C_5") (pintype "input"))
      (node (ref "IC29") (pin "1") (pinfunction "~{SYNC}_1") (pintype "input"))
      (node (ref "R168") (pin "1") (pinfunction "1_1") (pintype "passive"))
    )
    (net (code "22") (name "/RPI_SPI0_SS1") (class "Default")
      (node (ref "R166") (pin "1") (pinfunction "1_1") (pintype "passive"))
    )
    (net (code "23") (name "/RPI_SYNC_IN") (class "Default")
      (node (ref "J38") (pin "2") (pinfunction "2_2") (pintype "passive"))
    )
    (net (code "24") (name "/RPI_SYNC_IN_LS") (class "Default")
      (node (ref "IC56") (pin "4") (pinfunction "HSD1-_4") (pintype "passive"))
      (node (ref "IC56") (pin "7") (pinfunction "HSD2+_7") (pintype "passive"))
      (node (ref "R258") (pin "1") (pinfunction "1_1") (pintype "passive"))
    )
    (net (code "25") (name "/RPI_SYNC_OUT") (class "Default")
      (node (ref "J34") (pin "5") (pinfunction "5_5") (pintype "passive"))
      (node (ref "J36") (pin "1") (pinfunction "1_1") (pintype "passive"))
      (node (ref "J37") (pin "1") (pinfunction "1_1") (pintype "passive"))
    )
    (net (code "26") (name "/RPI_SYNC_OUT_LS") (class "Default")
      (node (ref "IC56") (pin "5") (pinfunction "HSD1+_5") (pintype "passive"))
      (node (ref "R272") (pin "1") (pinfunction "1_1") (pintype "passive"))
    )
    (net (code "27") (name "/TCXO_DAC_VREF") (class "Default")
      (node (ref "C126") (pin "2") (pinfunction "2_2") (pintype "passive"))
      (node (ref "C127") (pin "1") (pinfunction "1_1") (pintype "passive"))
      (node (ref "IC27") (pin "2") (pinfunction "Vref_2") (pintype "input"))
      (node (ref "R152") (pin "1") (pinfunction "1_1") (pintype "passive"))
      (node (ref "R153") (pin "1") (pinfunction "1_1") (pintype "passive"))
      (node (ref "R158") (pin "1") (pinfunction "1_1") (pintype "passive"))
    )
    (net (code "28") (name "/XO_VC") (class "Default")
      (node (ref "R149") (pin "1") (pinfunction "1_1") (pintype "passive"))
      (node (ref "R157") (pin "2") (pinfunction "2_2") (pintype "passive"))
      (node (ref "XO1") (pin "1") (pinfunction "NC/VC_1") (pintype "passive"))
      (node (ref "XO2") (pin "1") (pinfunction "VC_1") (pintype "passive"))
      (node (ref "XO3") (pin "1") (pinfunction "Vc_1") (pintype "passive"))
      (node (ref "XO4") (pin "1") (pinfunction "VCO_1") (pintype "input"))
      (node (ref "XO5") (pin "1") (pinfunction "Vcon_1") (pintype "passive"))
    )
    (net (code "29") (name "GND") (class "Default")
      (node (ref "C100") (pin "1") (pinfunction "1_1") (pintype "passive"))
      (node (ref "C101") (pin "1") (pinfunction "1_1") (pintype "passive"))
      (node (ref "C102") (pin "1") (pinfunction "1_1") (pintype "passive"))
      (node (ref "C103") (pin "1") (pinfunction "1_1") (pintype "passive"))
      (node (ref "C104") (pin "1") (pinfunction "1_1") (pintype "passive"))
      (node (ref "C105") (pin "1") (pinfunction "1_1") (pintype "passive"))
      (node (ref "C106") (pin "1") (pinfunction "1_1") (pintype "passive"))
      (node (ref "C107") (pin "1") (pinfunction "1_1") (pintype "passive"))
      (node (ref "C108") (pin "1") (pinfunction "1_1") (pintype "passive"))
      (node (ref "C109") (pin "1") (pinfunction "1_1") (pintype "passive"))
      (node (ref "C110") (pin "1") (pinfunction "1_1") (pintype "passive"))
      (node (ref "C111") (pin "2") (pinfunction "2_2") (pintype "passive"))
      (node (ref "C112") (pin "2") (pinfunction "2_2") (pintype "passive"))
      (node (ref "C115") (pin "1") (pinfunction "1_1") (pintype "passive"))
      (node (ref "C116") (pin "2") (pinfunction "2_2") (pintype "passive"))
      (node (ref "C117") (pin "2") (pinfunction "2_2") (pintype "passive"))
      (node (ref "C118") (pin "1") (pinfunction "1_1") (pintype "passive"))
      (node (ref "C119") (pin "2") (pinfunction "2_2") (pintype "passive"))
      (node (ref "C120") (pin "2") (pinfunction "2_2") (pintype "passive"))
      (node (ref "C121") (pin "1") (pinfunction "1_1") (pintype "passive"))
      (node (ref "C122") (pin "2") (pinfunction "2_2") (pintype "passive"))
      (node (ref "C123") (pin "2") (pinfunction "2_2") (pintype "passive"))
      (node (ref "C126") (pin "1") (pinfunction "1_1") (pintype "passive"))
      (node (ref "C127") (pin "2") (pinfunction "2_2") (pintype "passive"))
      (node (ref "C128") (pin "1") (pinfunction "1_1") (pintype "passive"))
      (node (ref "C130") (pin "1") (pinfunction "1_1") (pintype "passive"))
      (node (ref "C131") (pin "2") (pinfunction "2_2") (pintype "passive"))
      (node (ref "C132") (pin "2") (pinfunction "2_2") (pintype "passive"))
      (node (ref "C133") (pin "2") (pinfunction "2_2") (pintype "passive"))
      (node (ref "C246") (pin "2") (pinfunction "2_2") (pintype "passive"))
      (node (ref "C84") (pin "1") (pinfunction "1_1") (pintype "passive"))
      (node (ref "C85") (pin "1") (pinfunction "1_1") (pintype "passive"))
      (node (ref "C86") (pin "2") (pinfunction "2_2") (pintype "passive"))
      (node (ref "C89") (pin "1") (pinfunction "1_1") (pintype "passive"))
      (node (ref "C90") (pin "1") (pinfunction "1_1") (pintype "passive"))
      (node (ref "C91") (pin "1") (pinfunction "1_1") (pintype "passive"))
      (node (ref "C92") (pin "1") (pinfunction "1_1") (pintype "passive"))
      (node (ref "C93") (pin "1") (pinfunction "1_1") (pintype "passive"))
      (node (ref "C94") (pin "1") (pinfunction "1_1") (pintype "passive"))
      (node (ref "C95") (pin "1") (pinfunction "1_1") (pintype "passive"))
      (node (ref "C96") (pin "1") (pinfunction "1_1") (pintype "passive"))
      (node (ref "C97") (pin "1") (pinfunction "1_1") (pintype "passive"))
      (node (ref "C98") (pin "1") (pinfunction "1_1") (pintype "passive"))
      (node (ref "C99") (pin "1") (pinfunction "1_1") (pintype "passive"))
      (node (ref "IC25") (pin "1") (pinfunction "GND_1") (pintype "passive"))
      (node (ref "IC25") (pin "11") (pinfunction "GND_11") (pintype "passive"))
      (node (ref "IC25") (pin "12") (pinfunction "GND_12") (pintype "passive"))
      (node (ref "IC25") (pin "16") (pinfunction "GND_16") (pintype "passive"))
      (node (ref "IC25") (pin "19") (pinfunction "GND_19") (pintype "passive"))
      (node (ref "IC25") (pin "22") (pinfunction "SEL_22") (pintype "passive"))
      (node (ref "IC25") (pin "25") (pinfunction "GND_25") (pintype "passive"))
      (node (ref "IC25") (pin "7") (pinfunction "GND_7") (pintype "passive"))
      (node (ref "IC26") (pin "2") (pinfunction "GND_2") (pintype "passive"))
      (node (ref "IC27") (pin "8") (pinfunction "GND_8") (pintype "passive"))
      (node (ref "IC28") (pin "1") (pinfunction "CPGND_1") (pintype "passive"))
      (node (ref "IC28") (pin "10") (pinfunction "DGND_10") (pintype "passive"))
      (node (ref "IC28") (pin "2") (pinfunction "AGND_2") (pintype "passive"))
      (node (ref "IC28") (pin "21") (pinfunction "AGND_21") (pintype "passive"))
      (node (ref "IC28") (pin "3") (pinfunction "AGND_3") (pintype "passive"))
      (node (ref "IC28") (pin "9") (pinfunction "DGND_9") (pintype "passive"))
      (node (ref "IC29") (pin "5") (pinfunction "GND_5") (pintype "power_in"))
      (node (ref "IC56") (pin "3") (pinfunction "GND_3") (pintype "passive"))
      (node (ref "IC56") (pin "8") (pinfunction "~{OE}_8") (pintype "input"))
      (node (ref "J32") (pin "2") (pinfunction "Y_2") (pintype "passive"))
      (node (ref "J33") (pin "2") (pinfunction "Y_2") (pintype "passive"))
      (node (ref "J35") (pin "2") (pinfunction "Y_2") (pintype "passive"))
      (node (ref "R136") (pin "1") (pinfunction "1_1") (pintype "passive"))
      (node (ref "R150") (pin "1") (pinfunction "1_1") (pintype "passive"))
      (node (ref "R156") (pin "1") (pinfunction "1_1") (pintype "passive"))
      (node (ref "R158") (pin "2") (pinfunction "2_2") (pintype "passive"))
      (node (ref "R159") (pin "2") (pinfunction "2_2") (pintype "passive"))
      (node (ref "R160") (pin "2") (pinfunction "2_2") (pintype "passive"))
      (node (ref "R161") (pin "1") (pinfunction "1_1") (pintype "passive"))
      (node (ref "R167") (pin "2") (pinfunction "2_2") (pintype "passive"))
      (node (ref "R269") (pin "2") (pinfunction "2_2") (pintype "passive"))
      (node (ref "XO1") (pin "2") (pinfunction "GND_2") (pintype "passive"))
      (node (ref "XO2") (pin "2") (pinfunction "GND_2") (pintype "passive"))
      (node (ref "XO3") (pin "2") (pinfunction "GND_2") (pintype "passive"))
      (node (ref "XO4") (pin "4") (pinfunction "GND_4") (pintype "passive"))
      (node (ref "XO5") (pin "2") (pinfunction "GND_2") (pintype "passive"))
    )
    (net (code "30") (name "Net-(C87-Pad2)") (class "Default")
      (node (ref "C87") (pin "2") (pinfunction "2_2") (pintype "passive"))
      (node (ref "C88") (pin "1") (pinfunction "1_1") (pintype "passive"))
      (node (ref "R136") (pin "2") (pinfunction "2_2") (pintype "passive"))
    )
    (net (code "31") (name "Net-(C88-Pad2)") (class "Default")
      (node (ref "C88") (pin "2") (pinfunction "2_2") (pintype "passive"))
      (node (ref "R132") (pin "1") (pinfunction "1_1") (pintype "passive"))
      (node (ref "R138") (pin "1") (pinfunction "1_1") (pintype "passive"))
      (node (ref "R142") (pin "2") (pinfunction "2_2") (pintype "passive"))
      (node (ref "R145") (pin "1") (pinfunction "1_1") (pintype "passive"))
    )
    (net (code "32") (name "Net-(C110-Pad2)") (class "Default")
      (node (ref "C110") (pin "2") (pinfunction "2_2") (pintype "passive"))
      (node (ref "C111") (pin "1") (pinfunction "1_1") (pintype "passive"))
      (node (ref "C112") (pin "1") (pinfunction "1_1") (pintype "passive"))
      (node (ref "FR7") (pin "2") (pinfunction "2_2") (pintype "passive"))
      (node (ref "IC28") (pin "6") (pinfunction "AVdd_6") (pintype "passive"))
      (node (ref "IC28") (pin "7") (pinfunction "AVdd_7") (pintype "passive"))
    )
    (net (code "33") (name "Net-(C113-Pad2)") (class "Default")
      (node (ref "C113") (pin "2") (pinfunction "2_2") (pintype "passive"))
      (node (ref "C114") (pin "1") (pinfunction "1_1") (pintype "passive"))
      (node (ref "R150") (pin "2") (pinfunction "2_2") (pintype "passive"))
    )
    (net (code "34") (name "Net-(C118-Pad2)") (class "Default")
      (node (ref "C118") (pin "2") (pinfunction "2_2") (pintype "passive"))
      (node (ref "R148") (pin "1") (pinfunction "1_1") (pintype "passive"))
      (node (ref "R149") (pin "2") (pinfunction "2_2") (pintype "passive"))
      (node (ref "R162") (pin "2") (pinfunction "2_2") (pintype "passive"))
      (node (ref "R164") (pin "1") (pinfunction "1_1") (pintype "passive"))
      (node (ref "R167") (pin "1") (pinfunction "1_1") (pintype "passive"))
    )
    (net (code "35") (name "Net-(C124-Pad2)") (class "Default")
      (node (ref "C124") (pin "2") (pinfunction "2_2") (pintype "passive"))
      (node (ref "C125") (pin "1") (pinfunction "1_1") (pintype "passive"))
      (node (ref "R156") (pin "2") (pinfunction "2_2") (pintype "passive"))
    )
    (net (code "36") (name "Net-(C128-Pad2)") (class "Default")
      (node (ref "C128") (pin "2") (pinfunction "2_2") (pintype "passive"))
      (node (ref "R155") (pin "2") (pinfunction "2_2") (pintype "passive"))
      (node (ref "R157") (pin "1") (pinfunction "1_1") (pintype "passive"))
    )
    (net (code "37") (name "Net-(C129-Pad1)") (class "Default")
      (node (ref "C129") (pin "1") (pinfunction "1_1") (pintype "passive"))
      (node (ref "R161") (pin "2") (pinfunction "2_2") (pintype "passive"))
    )
    (net (code "38") (name "Net-(FR4-Pad2)") (class "Default")
      (node (ref "FR4") (pin "2") (pinfunction "2_2") (pintype "passive"))
      (node (ref "R133") (pin "1") (pinfunction "1_1") (pintype "passive"))
      (node (ref "R139") (pin "2") (pinfunction "2_2") (pintype "passive"))
      (node (ref "R140") (pin "1") (pinfunction "1_1") (pintype "passive"))
      (node (ref "R144") (pin "1") (pinfunction "1_1") (pintype "passive"))
    )
    (net (code "39") (name "Net-(IC25-CLKin)") (class "Default")
      (node (ref "C87") (pin "1") (pinfunction "1_1") (pintype "passive"))
      (node (ref "IC25") (pin "21") (pinfunction "CLKin_21") (pintype "passive"))
    )
    (net (code "40") (name "Net-(IC25-CLKin*)") (class "Default")
      (node (ref "C89") (pin "2") (pinfunction "2_2") (pintype "passive"))
      (node (ref "IC25") (pin "20") (pinfunction "CLKin*_20") (pintype "passive"))
    )
    (net (code "41") (name "Net-(IC25-OE)") (class "Default")
      (node (ref "IC25") (pin "24") (pinfunction "OE_24") (pintype "passive"))
      (node (ref "R134") (pin "1") (pinfunction "1_1") (pintype "passive"))
    )
    (net (code "42") (name "Net-(IC26-EN)") (class "Default")
      (node (ref "C105") (pin "2") (pinfunction "2_2") (pintype "passive"))
      (node (ref "C107") (pin "2") (pinfunction "2_2") (pintype "passive"))
      (node (ref "IC26") (pin "1") (pinfunction "IN_1") (pintype "input"))
      (node (ref "IC26") (pin "3") (pinfunction "EN_3") (pintype "input"))
      (node (ref "R144") (pin "2") (pinfunction "2_2") (pintype "passive"))
      (node (ref "R146") (pin "2") (pinfunction "2_2") (pintype "passive"))
    )
    (net (code "43") (name "Net-(IC26-OUT)") (class "Default")
      (node (ref "C106") (pin "2") (pinfunction "2_2") (pintype "passive"))
      (node (ref "C108") (pin "2") (pinfunction "2_2") (pintype "passive"))
      (node (ref "IC26") (pin "5") (pinfunction "OUT_5") (pintype "output"))
      (node (ref "R146") (pin "1") (pinfunction "1_1") (pintype "passive"))
      (node (ref "XO5") (pin "4") (pinfunction "VCC_4") (pintype "passive"))
    )
    (net (code "44") (name "Net-(IC27-Vdd)") (class "Default")
      (node (ref "C115") (pin "2") (pinfunction "2_2") (pintype "passive"))
      (node (ref "C116") (pin "1") (pinfunction "1_1") (pintype "passive"))
      (node (ref "C117") (pin "1") (pinfunction "1_1") (pintype "passive"))
      (node (ref "C133") (pin "1") (pinfunction "1_1") (pintype "passive"))
      (node (ref "FR8") (pin "1") (pinfunction "1_1") (pintype "passive"))
      (node (ref "IC27") (pin "1") (pinfunction "Vdd_1") (pintype "power_in"))
      (node (ref "IC29") (pin "4") (pinfunction "VDD_4") (pintype "power_in"))
      (node (ref "R153") (pin "2") (pinfunction "2_2") (pintype "passive"))
    )
    (net (code "45") (name "Net-(IC27-Vfb)") (class "Default")
      (node (ref "C122") (pin "1") (pinfunction "1_1") (pintype "passive"))
      (node (ref "IC27") (pin "3") (pinfunction "Vfb_3") (pintype "input"))
      (node (ref "IC27") (pin "4") (pinfunction "Vout_4") (pintype "output"))
      (node (ref "R148") (pin "2") (pinfunction "2_2") (pintype "passive"))
    )
    (net (code "46") (name "Net-(IC28-CE)") (class "Default")
      (node (ref "IC28") (pin "11") (pinfunction "CE_11") (pintype "passive"))
      (node (ref "R154") (pin "1") (pinfunction "1_1") (pintype "passive"))
    )
    (net (code "47") (name "Net-(IC28-CLK)") (class "Default")
      (node (ref "C132") (pin "1") (pinfunction "1_1") (pintype "passive"))
      (node (ref "IC28") (pin "12") (pinfunction "CLK_12") (pintype "passive"))
      (node (ref "R163") (pin "2") (pinfunction "2_2") (pintype "passive"))
    )
    (net (code "48") (name "Net-(IC28-CP)") (class "Default")
      (node (ref "C129") (pin "2") (pinfunction "2_2") (pintype "passive"))
      (node (ref "C130") (pin "2") (pinfunction "2_2") (pintype "passive"))
      (node (ref "IC28") (pin "20") (pinfunction "CP_20") (pintype "passive"))
      (node (ref "R155") (pin "1") (pinfunction "1_1") (pintype "passive"))
    )
    (net (code "49") (name "Net-(IC28-DATA)") (class "Default")
      (node (ref "IC28") (pin "13") (pinfunction "DATA_13") (pintype "passive"))
      (node (ref "R165") (pin "2") (pinfunction "2_2") (pintype "passive"))
    )
    (net (code "50") (name "Net-(IC28-LE)") (class "Default")
      (node (ref "IC28") (pin "14") (pinfunction "LE_14") (pintype "passive"))
      (node (ref "R166") (pin "2") (pinfunction "2_2") (pintype "passive"))
    )
    (net (code "51") (name "Net-(IC28-REFin)") (class "Default")
      (node (ref "C124") (pin "1") (pinfunction "1_1") (pintype "passive"))
      (node (ref "IC28") (pin "8") (pinfunction "REFin_8") (pintype "passive"))
    )
    (net (code "52") (name "Net-(IC28-RFinA)") (class "Default")
      (node (ref "C113") (pin "1") (pinfunction "1_1") (pintype "passive"))
      (node (ref "IC28") (pin "5") (pinfunction "RFinA_5") (pintype "passive"))
    )
    (net (code "53") (name "Net-(IC28-RFinB)") (class "Default")
      (node (ref "C131") (pin "1") (pinfunction "1_1") (pintype "passive"))
      (node (ref "IC28") (pin "4") (pinfunction "RFinB_4") (pintype "passive"))
    )
    (net (code "54") (name "Net-(IC28-Rset)") (class "Default")
      (node (ref "IC28") (pin "19") (pinfunction "Rset_19") (pintype "passive"))
      (node (ref "R160") (pin "1") (pinfunction "1_1") (pintype "passive"))
    )
    (net (code "55") (name "Net-(IC28-Vp)") (class "Default")
      (node (ref "C121") (pin "2") (pinfunction "2_2") (pintype "passive"))
      (node (ref "C123") (pin "1") (pinfunction "1_1") (pintype "passive"))
      (node (ref "IC28") (pin "18") (pinfunction "Vp_18") (pintype "passive"))
      (node (ref "R151") (pin "1") (pinfunction "1_1") (pintype "passive"))
    )
    (net (code "56") (name "Net-(IC29-VOUT)") (class "Default")
      (node (ref "IC29") (pin "6") (pinfunction "VOUT_6") (pintype "tri_state"))
      (node (ref "R164") (pin "2") (pinfunction "2_2") (pintype "passive"))
    )
    (net (code "57") (name "Net-(J33-X)") (class "Default")
      (node (ref "J33") (pin "1") (pinfunction "X_1") (pintype "passive"))
      (node (ref "R135") (pin "1") (pinfunction "1_1") (pintype "passive"))
    )
    (net (code "58") (name "Net-(J37-Pad2)") (class "Default")
      (node (ref "J37") (pin "2") (pinfunction "2_2") (pintype "passive"))
      (node (ref "R141") (pin "1") (pinfunction "1_1") (pintype "passive"))
    )
    (net (code "59") (name "Net-(R140-Pad2)") (class "Default")
      (node (ref "R140") (pin "2") (pinfunction "2_2") (pintype "passive"))
      (node (ref "R143") (pin "1") (pinfunction "1_1") (pintype "passive"))
    )
    (net (code "60") (name "Net-(XO1-Output)") (class "Default")
      (node (ref "R132") (pin "2") (pinfunction "2_2") (pintype "passive"))
      (node (ref "XO1") (pin "3") (pinfunction "Output_3") (pintype "output"))
    )
    (net (code "61") (name "Net-(XO1-Vcc)") (class "Default")
      (node (ref "C84") (pin "2") (pinfunction "2_2") (pintype "passive"))
      (node (ref "C85") (pin "2") (pinfunction "2_2") (pintype "passive"))
      (node (ref "C86") (pin "1") (pinfunction "1_1") (pintype "passive"))
      (node (ref "R133") (pin "2") (pinfunction "2_2") (pintype "passive"))
      (node (ref "XO1") (pin "4") (pinfunction "Vcc_4") (pintype "power_in"))
    )
    (net (code "62") (name "Net-(XO2-OUT)") (class "Default")
      (node (ref "R138") (pin "2") (pinfunction "2_2") (pintype "passive"))
      (node (ref "XO2") (pin "4") (pinfunction "OUT_4") (pintype "passive"))
      (node (ref "XO3") (pin "3") (pinfunction "OUT_3") (pintype "passive"))
    )
    (net (code "63") (name "Net-(XO2-TRI-ST.)") (class "Default")
      (node (ref "R137") (pin "1") (pinfunction "1_1") (pintype "passive"))
      (node (ref "XO2") (pin "6") (pinfunction "TRI-ST._6") (pintype "passive"))
    )
    (net (code "64") (name "Net-(XO2-VDD)") (class "Default")
      (node (ref "C90") (pin "2") (pinfunction "2_2") (pintype "passive"))
      (node (ref "C91") (pin "2") (pinfunction "2_2") (pintype "passive"))
      (node (ref "R137") (pin "2") (pinfunction "2_2") (pintype "passive"))
      (node (ref "R139") (pin "1") (pinfunction "1_1") (pintype "passive"))
      (node (ref "XO2") (pin "5") (pinfunction "VDD_5") (pintype "passive"))
      (node (ref "XO3") (pin "4") (pinfunction "VDD_4") (pintype "passive"))
    )
    (net (code "65") (name "Net-(XO4-RF_OUT)") (class "Default")
      (node (ref "R142") (pin "1") (pinfunction "1_1") (pintype "passive"))
      (node (ref "XO4") (pin "6") (pinfunction "RF_OUT_6") (pintype "output"))
    )
    (net (code "66") (name "Net-(XO4-VCC)") (class "Default")
      (node (ref "C96") (pin "2") (pinfunction "2_2") (pintype "passive"))
      (node (ref "C97") (pin "2") (pinfunction "2_2") (pintype "passive"))
      (node (ref "R143") (pin "2") (pinfunction "2_2") (pintype "passive"))
      (node (ref "XO4") (pin "9") (pinfunction "VCC_9") (pintype "power_in"))
    )
    (net (code "67") (name "Net-(XO4-VC_FILTER)") (class "Default")
      (node (ref "C98") (pin "2") (pinfunction "2_2") (pintype "passive"))
      (node (ref "XO4") (pin "7") (pinfunction "VC_FILTER_7") (pintype "input"))
    )
    (net (code "68") (name "Net-(XO5-OUT)") (class "Default")
      (node (ref "R145") (pin "2") (pinfunction "2_2") (pintype "passive"))
      (node (ref "R147") (pin "1") (pinfunction "1_1") (pintype "passive"))
      (node (ref "XO5") (pin "3") (pinfunction "OUT_3") (pintype "passive"))
    )
    (net (code "69") (name "VCC2P5_VREF") (class "Default")
      (node (ref "R152") (pin "2") (pinfunction "2_2") (pintype "passive"))
    )
    (net (code "70") (name "VCC3P3") (class "Default")
      (node (ref "C246") (pin "1") (pinfunction "1_1") (pintype "passive"))
      (node (ref "IC56") (pin "9") (pinfunction "VCC_9") (pintype "power_in"))
    )
    (net (code "71") (name "VCC3P3_CLK") (class "Default")
      (node (ref "C109") (pin "2") (pinfunction "2_2") (pintype "passive"))
      (node (ref "C119") (pin "1") (pinfunction "1_1") (pintype "passive"))
      (node (ref "C120") (pin "1") (pinfunction "1_1") (pintype "passive"))
      (node (ref "FR4") (pin "1") (pinfunction "1_1") (pintype "passive"))
      (node (ref "FR5") (pin "1") (pinfunction "1_1") (pintype "passive"))
      (node (ref "FR6") (pin "1") (pinfunction "1_1") (pintype "passive"))
      (node (ref "FR7") (pin "1") (pinfunction "1_1") (pintype "passive"))
      (node (ref "FR8") (pin "2") (pinfunction "2_2") (pintype "passive"))
      (node (ref "IC28") (pin "16") (pinfunction "DVdd_16") (pintype "passive"))
      (node (ref "IC28") (pin "17") (pinfunction "DVdd_17") (pintype "passive"))
      (node (ref "R151") (pin "2") (pinfunction "2_2") (pintype "passive"))
      (node (ref "R154") (pin "2") (pinfunction "2_2") (pintype "passive"))
      (node (ref "R162") (pin "1") (pinfunction "1_1") (pintype "passive"))
    )
    (net (code "72") (name "VCC3P3_LMK") (class "Default")
      (node (ref "C92") (pin "2") (pinfunction "2_2") (pintype "passive"))
      (node (ref "C93") (pin "2") (pinfunction "2_2") (pintype "passive"))
      (node (ref "C94") (pin "2") (pinfunction "2_2") (pintype "passive"))
      (node (ref "C95") (pin "2") (pinfunction "2_2") (pintype "passive"))
      (node (ref "FR5") (pin "2") (pinfunction "2_2") (pintype "passive"))
      (node (ref "IC25") (pin "23") (pinfunction "Vdd_23") (pintype "passive"))
      (node (ref "IC25") (pin "8") (pinfunction "Vdd_8") (pintype "passive"))
      (node (ref "R134") (pin "2") (pinfunction "2_2") (pintype "passive"))
    )
    (net (code "73") (name "VCC3P3_LMK_VDDO") (class "Default")
      (node (ref "C100") (pin "2") (pinfunction "2_2") (pintype "passive"))
      (node (ref "C101") (pin "2") (pinfunction "2_2") (pintype "passive"))
      (node (ref "C102") (pin "2") (pinfunction "2_2") (pintype "passive"))
      (node (ref "C103") (pin "2") (pinfunction "2_2") (pintype "passive"))
      (node (ref "C104") (pin "2") (pinfunction "2_2") (pintype "passive"))
      (node (ref "C99") (pin "2") (pinfunction "2_2") (pintype "passive"))
      (node (ref "FR6") (pin "2") (pinfunction "2_2") (pintype "passive"))
      (node (ref "IC25") (pin "14") (pinfunction "Vddo_14") (pintype "passive"))
      (node (ref "IC25") (pin "18") (pinfunction "Vddo_18") (pintype "passive"))
      (node (ref "IC25") (pin "2") (pinfunction "Vddo_2") (pintype "passive"))
      (node (ref "IC25") (pin "6") (pinfunction "Vddo_6") (pintype "passive"))
    )
    (net (code "74") (name "unconnected-(IC25-CLKout4-Pad17)") (class "Default")
      (node (ref "IC25") (pin "17") (pinfunction "CLKout4_17") (pintype "passive+no_connect"))
    )
    (net (code "75") (name "unconnected-(IC25-OSCin-Pad9)") (class "Default")
      (node (ref "IC25") (pin "9") (pinfunction "OSCin_9") (pintype "passive+no_connect"))
    )
    (net (code "76") (name "unconnected-(IC25-OSCout-Pad10)") (class "Default")
      (node (ref "IC25") (pin "10") (pinfunction "OSCout_10") (pintype "passive+no_connect"))
    )
    (net (code "77") (name "unconnected-(IC26-NC-Pad4)") (class "Default")
      (node (ref "IC26") (pin "4") (pinfunction "NC_4") (pintype "passive+no_connect"))
    )
    (net (code "78") (name "unconnected-(IC56-HSD2--Pad6)") (class "Default")
      (node (ref "IC56") (pin "6") (pinfunction "HSD2-_6") (pintype "passive+no_connect"))
    )
    (net (code "79") (name "unconnected-(JMP2-Pad1)") (class "Default")
      (node (ref "JMP2") (pin "1") (pinfunction "1_1") (pintype "passive"))
    )
    (net (code "80") (name "unconnected-(JMP2-Pad2)") (class "Default")
      (node (ref "JMP2") (pin "2") (pinfunction "2_2") (pintype "passive"))
    )
    (net (code "81") (name "unconnected-(JMP3-Pad1)") (class "Default")
      (node (ref "JMP3") (pin "1") (pinfunction "1_1") (pintype "passive"))
    )
    (net (code "82") (name "unconnected-(JMP3-Pad2)") (class "Default")
      (node (ref "JMP3") (pin "2") (pinfunction "2_2") (pintype "passive"))
    )
    (net (code "83") (name "unconnected-(JMP4-Pad1)") (class "Default")
      (node (ref "JMP4") (pin "1") (pinfunction "1_1") (pintype "passive"))
    )
    (net (code "84") (name "unconnected-(JMP4-Pad2)") (class "Default")
      (node (ref "JMP4") (pin "2") (pinfunction "2_2") (pintype "passive"))
    )
    (net (code "85") (name "unconnected-(JMP5-Pad1)") (class "Default")
      (node (ref "JMP5") (pin "1") (pinfunction "1_1") (pintype "passive"))
    )
    (net (code "86") (name "unconnected-(JMP5-Pad2)") (class "Default")
      (node (ref "JMP5") (pin "2") (pinfunction "2_2") (pintype "passive"))
    )
    (net (code "87") (name "unconnected-(JMP6-Pad1)") (class "Default")
      (node (ref "JMP6") (pin "1") (pinfunction "1_1") (pintype "passive"))
    )
    (net (code "88") (name "unconnected-(JMP6-Pad2)") (class "Default")
      (node (ref "JMP6") (pin "2") (pinfunction "2_2") (pintype "passive"))
    )
    (net (code "89") (name "unconnected-(XO2-T.S.-Pad3)") (class "Default")
      (node (ref "XO2") (pin "3") (pinfunction "T.S._3") (pintype "passive+no_connect"))
    )
    (net (code "90") (name "unconnected-(XO4-NC-Pad2)") (class "Default")
      (node (ref "XO4") (pin "2") (pinfunction "NC_2") (pintype "passive+no_connect"))
    )
    (net (code "91") (name "unconnected-(XO4-NC-Pad3)") (class "Default")
      (node (ref "XO4") (pin "3") (pinfunction "NC_3") (pintype "passive+no_connect"))
    )
    (net (code "92") (name "unconnected-(XO4-NC-Pad5)") (class "Default")
      (node (ref "XO4") (pin "5") (pinfunction "NC_5") (pintype "passive+no_connect"))
    )
    (net (code "93") (name "unconnected-(XO4-NC-Pad8)") (class "Default")
      (node (ref "XO4") (pin "8") (pinfunction "NC_8") (pintype "passive+no_connect"))
    )
    (net (code "94") (name "unconnected-(XO4-NC-Pad10)") (class "Default")
      (node (ref "XO4") (pin "10") (pinfunction "NC_10") (pintype "passive+no_connect"))
    )
  )
)
